# serpentine.net
KiCad netlist of a schematic drawn in Altium Designer
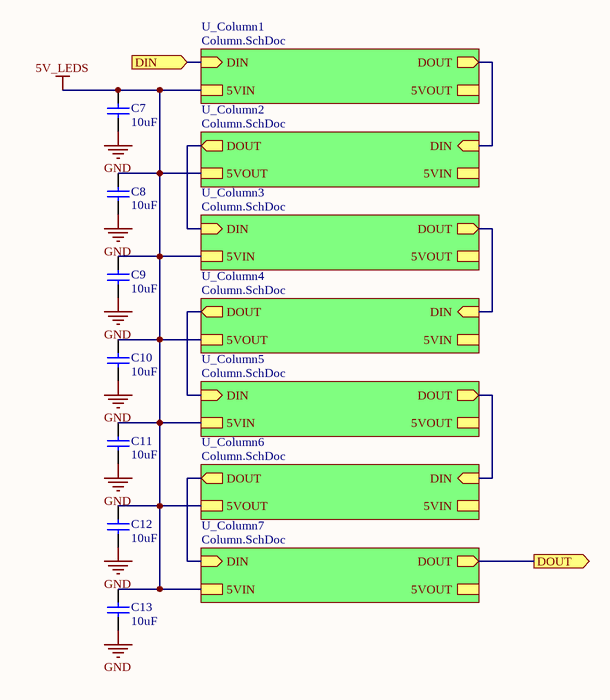
[diagram p0: serpentine.SchDoc]

(export (version "E")
  (design (tool "Eeschema 10.0.6"))
  (components
    (comp (ref "C7")
      (value "10uF")
      (footprint "CAP1206")
      (description "C342827")
      (fields (field (name "TOLERANCE") "10%"))
      (libsource (lib "blandat") (part "CAP"))
    )
    (comp (ref "C8")
      (value "10uF")
      (footprint "CAP1206")
      (description "C342827")
      (fields (field (name "TOLERANCE") "10%"))
      (libsource (lib "blandat") (part "CAP"))
    )
    (comp (ref "C9")
      (value "10uF")
      (footprint "CAP1206")
      (description "C342827")
      (fields (field (name "TOLERANCE") "10%"))
      (libsource (lib "blandat") (part "CAP"))
    )
    (comp (ref "C10")
      (value "10uF")
      (footprint "CAP1206")
      (description "C342827")
      (fields (field (name "TOLERANCE") "10%"))
      (libsource (lib "blandat") (part "CAP"))
    )
    (comp (ref "C11")
      (value "10uF")
      (footprint "CAP1206")
      (description "C342827")
      (fields (field (name "TOLERANCE") "10%"))
      (libsource (lib "blandat") (part "CAP"))
    )
    (comp (ref "C12")
      (value "10uF")
      (footprint "CAP1206")
      (description "C342827")
      (fields (field (name "TOLERANCE") "10%"))
      (libsource (lib "blandat") (part "CAP"))
    )
    (comp (ref "C13")
      (value "10uF")
      (footprint "CAP1206")
      (description "C342827")
      (fields (field (name "TOLERANCE") "10%"))
      (libsource (lib "blandat") (part "CAP"))
    )
  )
  (nets
    (net (code "16") (name "5V_LEDS") (class "Default")
      (node (ref "C10") (pin "2") (pinfunction "2_2") (pintype "passive"))
      (node (ref "C11") (pin "2") (pinfunction "2_2") (pintype "passive"))
      (node (ref "C12") (pin "2") (pinfunction "2_2") (pintype "passive"))
      (node (ref "C13") (pin "2") (pinfunction "2_2") (pintype "passive"))
      (node (ref "C7") (pin "2") (pinfunction "2_2") (pintype "passive"))
      (node (ref "C8") (pin "2") (pinfunction "2_2") (pintype "passive"))
      (node (ref "C9") (pin "2") (pinfunction "2_2") (pintype "passive"))
    )
    (net (code "17") (name "GND") (class "Default")
      (node (ref "C10") (pin "1") (pinfunction "1_1") (pintype "passive"))
      (node (ref "C11") (pin "1") (pinfunction "1_1") (pintype "passive"))
      (node (ref "C12") (pin "1") (pinfunction "1_1") (pintype "passive"))
      (node (ref "C13") (pin "1") (pinfunction "1_1") (pintype "passive"))
      (node (ref "C7") (pin "1") (pinfunction "1_1") (pintype "passive"))
      (node (ref "C8") (pin "1") (pinfunction "1_1") (pintype "passive"))
      (node (ref "C9") (pin "1") (pinfunction "1_1") (pintype "passive"))
    )
  )
)
